# diffamp.net
KiCad netlist of a schematic drawn in EAGLE
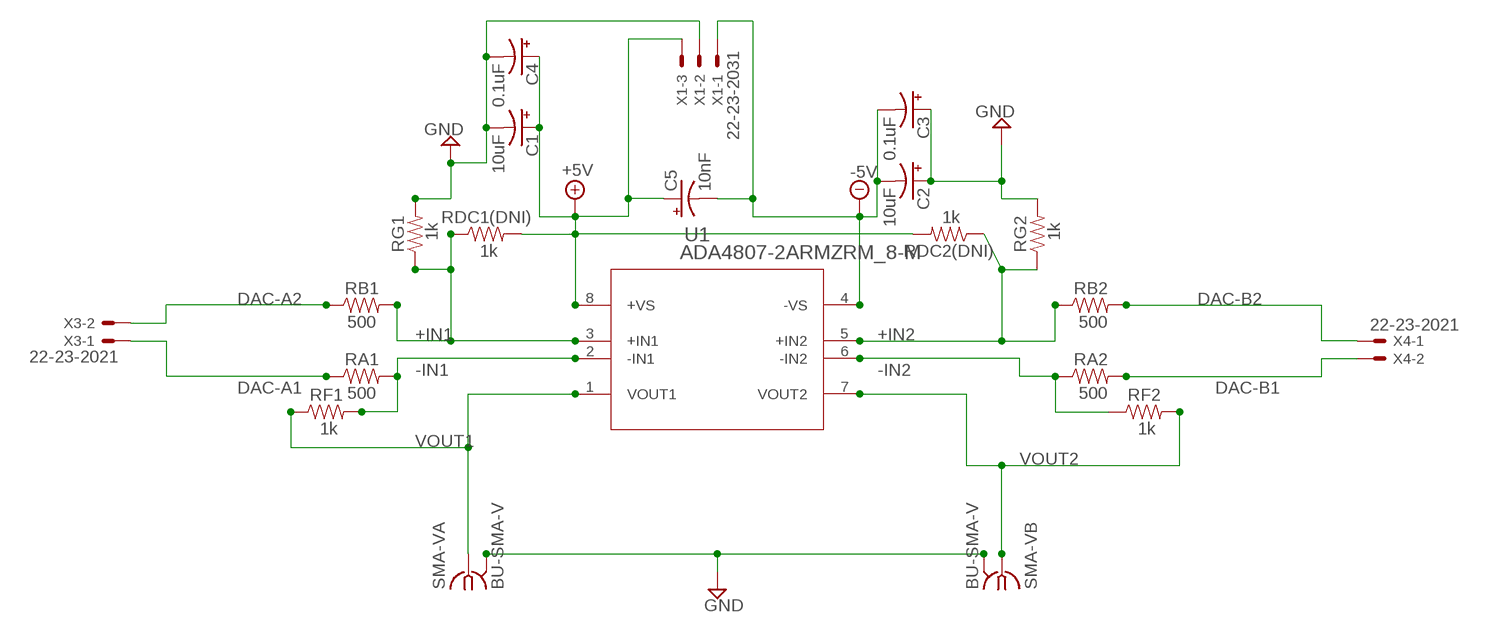
[diagram p0: schematic, sheet 1]

(export (version "E")
  (design (tool "Eeschema 10.0.6"))
  (components
    (comp (ref "C1")
      (value "10uF")
      (footprint "eagle-import:CPOL-RADIAL-2.5MM-5MM")
      (libsource (lib "eagle-import") (part "10UF-POLAR-RADIAL-2.5MM-25V-20%"))
    )
    (comp (ref "C2")
      (value "10uF")
      (footprint "eagle-import:CPOL-RADIAL-2.5MM-5MM")
      (libsource (lib "eagle-import") (part "10UF-POLAR-RADIAL-2.5MM-25V-20%"))
    )
    (comp (ref "C3")
      (value "0.1uF")
      (footprint "eagle-import:CPOL-RADIAL-2.5MM-5MM")
      (libsource (lib "eagle-import") (part "10UF-POLAR-RADIAL-2.5MM-25V-20%"))
    )
    (comp (ref "C4")
      (value "0.1uF")
      (footprint "eagle-import:CPOL-RADIAL-2.5MM-5MM")
      (libsource (lib "eagle-import") (part "10UF-POLAR-RADIAL-2.5MM-25V-20%"))
    )
    (comp (ref "C5")
      (value "10nF")
      (footprint "eagle-import:CPOL-RADIAL-2.5MM-5MM")
      (libsource (lib "eagle-import") (part "10UF-POLAR-RADIAL-2.5MM-25V-20%"))
    )
    (comp (ref "RA1")
      (value "500")
      (footprint "eagle-import:AXIAL-0.3")
      (libsource (lib "eagle-import") (part "RESISTORAXIAL-0.3"))
    )
    (comp (ref "RA2")
      (value "500")
      (footprint "eagle-import:AXIAL-0.3")
      (libsource (lib "eagle-import") (part "RESISTORAXIAL-0.3"))
    )
    (comp (ref "RB1")
      (value "500")
      (footprint "eagle-import:AXIAL-0.3")
      (libsource (lib "eagle-import") (part "RESISTORAXIAL-0.3"))
    )
    (comp (ref "RB2")
      (value "500")
      (footprint "eagle-import:AXIAL-0.3")
      (libsource (lib "eagle-import") (part "RESISTORAXIAL-0.3"))
    )
    (comp (ref "RDC1(DNI)")
      (value "1k")
      (footprint "eagle-import:AXIAL-0.3")
      (libsource (lib "eagle-import") (part "RESISTORAXIAL-0.3"))
    )
    (comp (ref "RDC2(DNI)")
      (value "1k")
      (footprint "eagle-import:AXIAL-0.3")
      (libsource (lib "eagle-import") (part "RESISTORAXIAL-0.3"))
    )
    (comp (ref "RF1")
      (value "1k")
      (footprint "eagle-import:AXIAL-0.3")
      (libsource (lib "eagle-import") (part "RESISTORAXIAL-0.3"))
    )
    (comp (ref "RF2")
      (value "1k")
      (footprint "eagle-import:AXIAL-0.3")
      (libsource (lib "eagle-import") (part "RESISTORAXIAL-0.3"))
    )
    (comp (ref "RG1")
      (value "1k")
      (footprint "eagle-import:AXIAL-0.3")
      (libsource (lib "eagle-import") (part "RESISTORAXIAL-0.3"))
    )
    (comp (ref "RG2")
      (value "1k")
      (footprint "eagle-import:AXIAL-0.3")
      (libsource (lib "eagle-import") (part "RESISTORAXIAL-0.3"))
    )
    (comp (ref "SMA-VA")
      (value "BU-SMA-V")
      (footprint "eagle-import:BU-SMA-V")
      (libsource (lib "eagle-import") (part "BU-SMA-V"))
    )
    (comp (ref "SMA-VB")
      (value "BU-SMA-V")
      (footprint "eagle-import:BU-SMA-V")
      (libsource (lib "eagle-import") (part "BU-SMA-V"))
    )
    (comp (ref "U1")
      (value "ADA4807-2ARMZRM_8-M")
      (footprint "eagle-import:RM_8-M")
      (fields (field (name "MANUFACTURER_PART_NUMBER") "ADA48072ARMZ"))
      (libsource (lib "eagle-import") (part "ADA4807-2ARMZRM_8-M"))
    )
    (comp (ref "X1")
      (value "22-23-2031")
      (footprint "eagle-import:22-23-2031")
      (fields (field (name "MF") "MOLEX"))
      (libsource (lib "eagle-import") (part "22-23-2031"))
    )
    (comp (ref "X3")
      (value "22-23-2021")
      (footprint "eagle-import:22-23-2021")
      (fields (field (name "MF") "MOLEX"))
      (libsource (lib "eagle-import") (part "22-23-2021"))
    )
    (comp (ref "X4")
      (value "22-23-2021")
      (footprint "eagle-import:22-23-2021")
      (fields (field (name "MF") "MOLEX"))
      (libsource (lib "eagle-import") (part "22-23-2021"))
    )
  )
  (nets
    (net (code "1") (name "+5V") (class "Default")
      (node (ref "C1") (pin "1") (pinfunction "+_1") (pintype "passive"))
      (node (ref "C4") (pin "1") (pinfunction "+_1") (pintype "passive"))
      (node (ref "C5") (pin "1") (pinfunction "+_1") (pintype "passive"))
      (node (ref "RDC1(DNI)") (pin "P$2") (pinfunction "2_P$2") (pintype "passive"))
      (node (ref "RDC2(DNI)") (pin "P$2") (pinfunction "2_P$2") (pintype "passive"))
      (node (ref "U1") (pin "8") (pinfunction "+VS_8") (pintype "passive"))
      (node (ref "X1") (pin "3") (pinfunction "S_3") (pintype "passive"))
    )
    (net (code "2") (name "-5V") (class "Default")
      (node (ref "C2") (pin "2") (pinfunction "-_2") (pintype "passive"))
      (node (ref "C3") (pin "2") (pinfunction "-_2") (pintype "passive"))
      (node (ref "C5") (pin "2") (pinfunction "-_2") (pintype "passive"))
      (node (ref "U1") (pin "4") (pinfunction "-VS_4") (pintype "passive"))
      (node (ref "X1") (pin "1") (pinfunction "S_1") (pintype "passive"))
    )
    (net (code "3") (name "/+IN1") (class "Default")
      (node (ref "RB1") (pin "P$2") (pinfunction "2_P$2") (pintype "passive"))
      (node (ref "RDC1(DNI)") (pin "P$1") (pinfunction "1_P$1") (pintype "passive"))
      (node (ref "RG1") (pin "P$1") (pinfunction "1_P$1") (pintype "passive"))
      (node (ref "U1") (pin "3") (pinfunction "+IN1_3") (pintype "passive"))
    )
    (net (code "4") (name "/+IN2") (class "Default")
      (node (ref "RB2") (pin "P$1") (pinfunction "1_P$1") (pintype "passive"))
      (node (ref "RDC2(DNI)") (pin "P$1") (pinfunction "1_P$1") (pintype "passive"))
      (node (ref "RG2") (pin "P$1") (pinfunction "1_P$1") (pintype "passive"))
      (node (ref "U1") (pin "5") (pinfunction "+IN2_5") (pintype "passive"))
    )
    (net (code "5") (name "/-IN1") (class "Default")
      (node (ref "RA1") (pin "P$2") (pinfunction "2_P$2") (pintype "passive"))
      (node (ref "RF1") (pin "P$2") (pinfunction "2_P$2") (pintype "passive"))
      (node (ref "U1") (pin "2") (pinfunction "-IN1_2") (pintype "passive"))
    )
    (net (code "6") (name "/-IN2") (class "Default")
      (node (ref "RA2") (pin "P$1") (pinfunction "1_P$1") (pintype "passive"))
      (node (ref "RF2") (pin "P$1") (pinfunction "1_P$1") (pintype "passive"))
      (node (ref "U1") (pin "6") (pinfunction "-IN2_6") (pintype "passive"))
    )
    (net (code "7") (name "/DAC-A1") (class "Default")
      (node (ref "RA1") (pin "P$1") (pinfunction "1_P$1") (pintype "passive"))
      (node (ref "X3") (pin "1") (pinfunction "S_1") (pintype "passive"))
    )
    (net (code "8") (name "/DAC-A2") (class "Default")
      (node (ref "RB1") (pin "P$1") (pinfunction "1_P$1") (pintype "passive"))
      (node (ref "X3") (pin "2") (pinfunction "S_2") (pintype "passive"))
    )
    (net (code "9") (name "/DAC-B1") (class "Default")
      (node (ref "RA2") (pin "P$2") (pinfunction "2_P$2") (pintype "passive"))
      (node (ref "X4") (pin "2") (pinfunction "S_2") (pintype "passive"))
    )
    (net (code "10") (name "/DAC-B2") (class "Default")
      (node (ref "RB2") (pin "P$2") (pinfunction "2_P$2") (pintype "passive"))
      (node (ref "X4") (pin "1") (pinfunction "S_1") (pintype "passive"))
    )
    (net (code "11") (name "/VOUT1") (class "Default")
      (node (ref "RF1") (pin "P$1") (pinfunction "1_P$1") (pintype "passive"))
      (node (ref "SMA-VA") (pin "1") (pinfunction "1_1") (pintype "passive"))
      (node (ref "U1") (pin "1") (pinfunction "VOUT1_1") (pintype "passive"))
    )
    (net (code "12") (name "/VOUT2") (class "Default")
      (node (ref "RF2") (pin "P$2") (pinfunction "2_P$2") (pintype "passive"))
      (node (ref "SMA-VB") (pin "1") (pinfunction "1_1") (pintype "passive"))
      (node (ref "U1") (pin "7") (pinfunction "VOUT2_7") (pintype "passive"))
    )
    (net (code "13") (name "GND") (class "Default")
      (node (ref "C1") (pin "2") (pinfunction "-_2") (pintype "passive"))
      (node (ref "C2") (pin "1") (pinfunction "+_1") (pintype "passive"))
      (node (ref "C3") (pin "1") (pinfunction "+_1") (pintype "passive"))
      (node (ref "C4") (pin "2") (pinfunction "-_2") (pintype "passive"))
      (node (ref "RG1") (pin "P$2") (pinfunction "2_P$2") (pintype "passive"))
      (node (ref "RG2") (pin "P$2") (pinfunction "2_P$2") (pintype "passive"))
      (node (ref "SMA-VA") (pin "2") (pinfunction "2_2") (pintype "passive"))
      (node (ref "SMA-VA") (pin "3") (pinfunction "2_3") (pintype "passive"))
      (node (ref "SMA-VA") (pin "4") (pinfunction "2_4") (pintype "passive"))
      (node (ref "SMA-VA") (pin "5") (pinfunction "2_5") (pintype "passive"))
      (node (ref "SMA-VB") (pin "2") (pinfunction "2_2") (pintype "passive"))
      (node (ref "SMA-VB") (pin "3") (pinfunction "2_3") (pintype "passive"))
      (node (ref "SMA-VB") (pin "4") (pinfunction "2_4") (pintype "passive"))
      (node (ref "SMA-VB") (pin "5") (pinfunction "2_5") (pintype "passive"))
      (node (ref "X1") (pin "2") (pinfunction "S_2") (pintype "passive"))
    )
  )
)
